# G020H.net
KiCad netlist of a schematic drawn in EAGLE
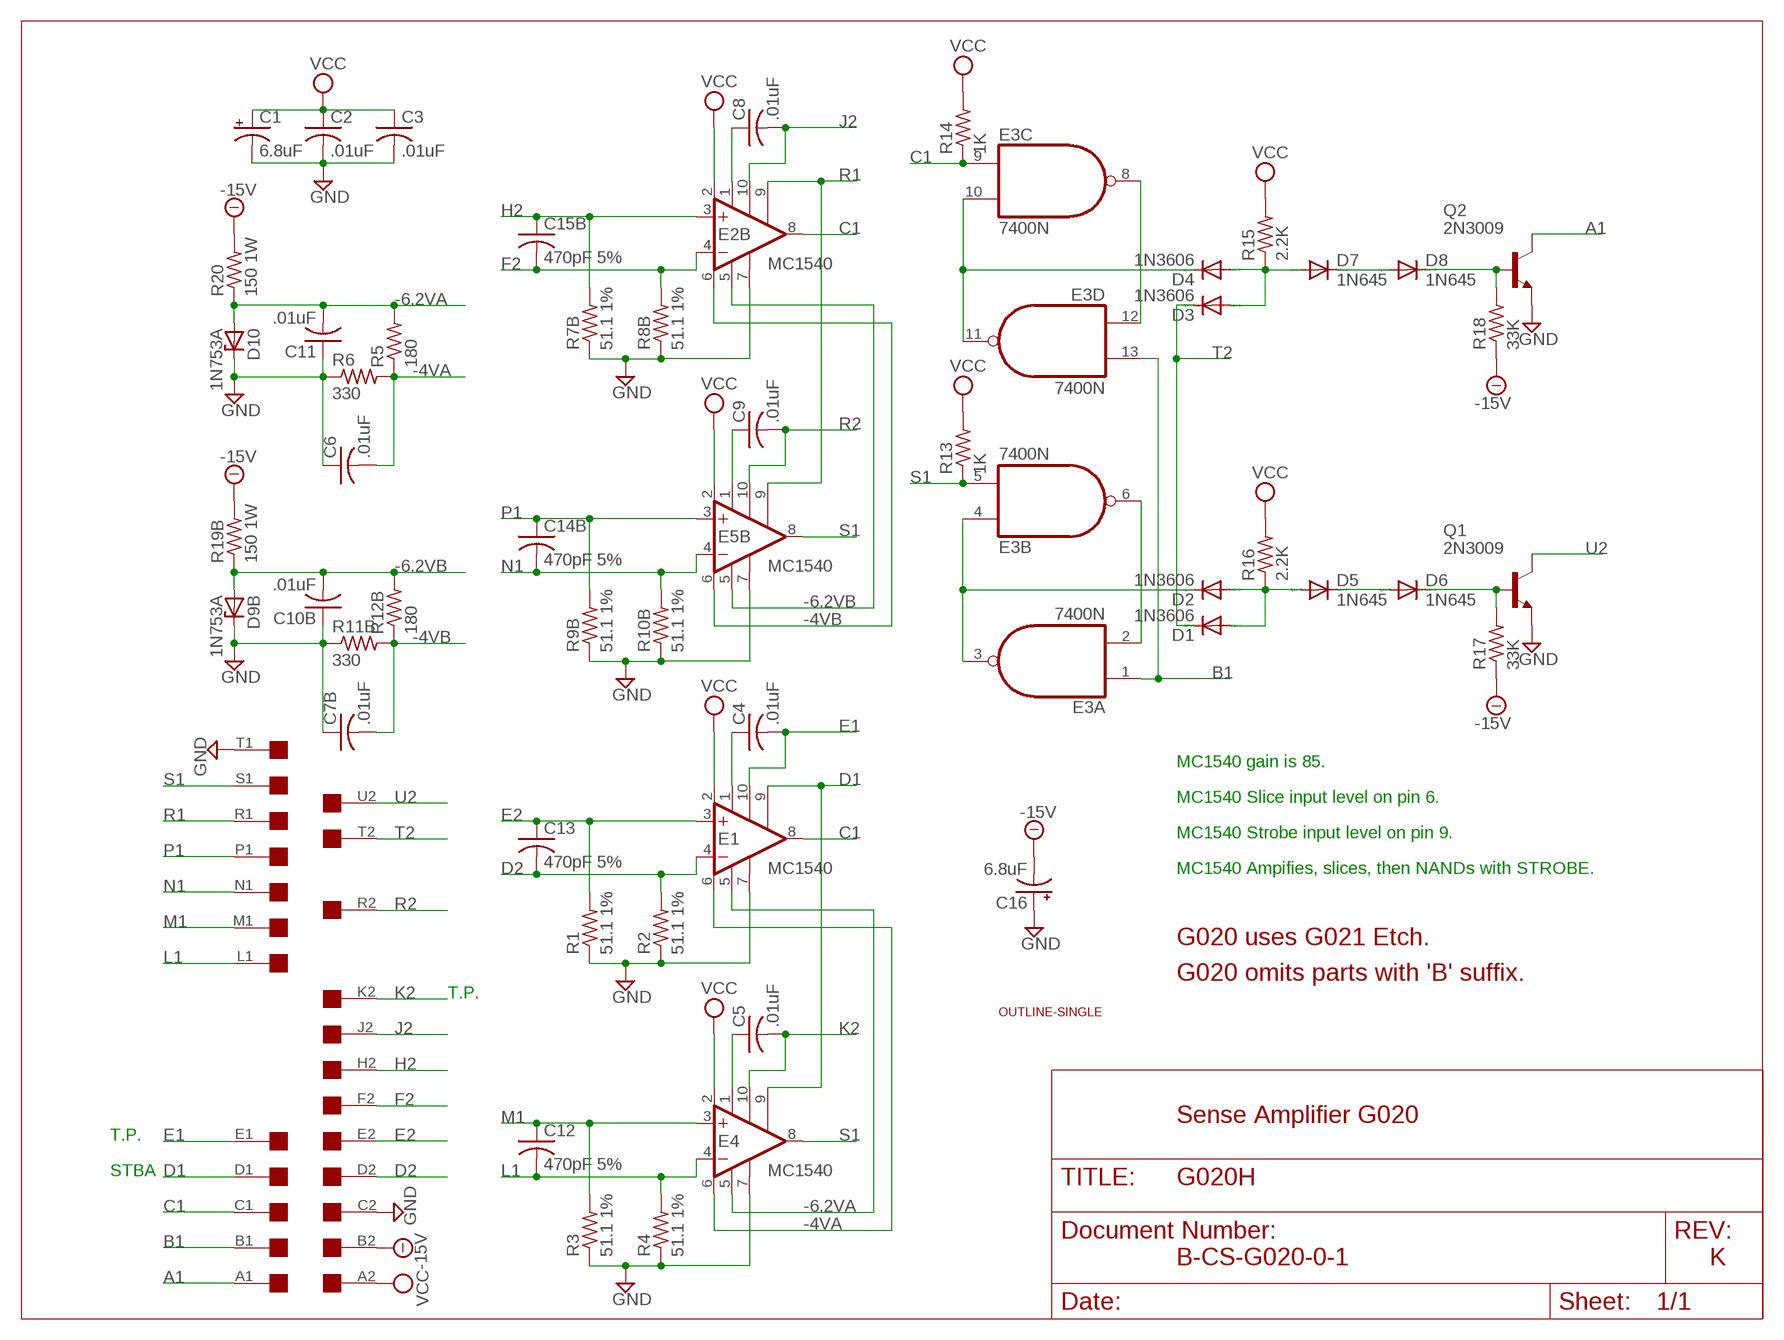
[diagram p0: schematic, sheet 1]

(export (version "E")
  (design (tool "Eeschema 10.0.6"))
  (components
    (comp (ref "C1")
      (value "6.8uF")
      (footprint "eagle-import:E12-8")
      (libsource (lib "eagle-import") (part "CPOL-USE20-8AXIAL"))
    )
    (comp (ref "C2")
      (value ".01uF")
      (footprint "eagle-import:C050-025X075")
      (libsource (lib "eagle-import") (part "C-US050-025X075"))
    )
    (comp (ref "C3")
      (value ".01uF")
      (footprint "eagle-import:C050-025X075")
      (libsource (lib "eagle-import") (part "C-US050-025X075"))
    )
    (comp (ref "C4")
      (value ".01uF")
      (footprint "eagle-import:C050-025X075")
      (libsource (lib "eagle-import") (part "C-US050-025X075"))
    )
    (comp (ref "C5")
      (value ".01uF")
      (footprint "eagle-import:C050-025X075")
      (libsource (lib "eagle-import") (part "C-US050-025X075"))
    )
    (comp (ref "C6")
      (value ".01uF")
      (footprint "eagle-import:C050-025X075")
      (libsource (lib "eagle-import") (part "C-US050-025X075"))
    )
    (comp (ref "C7B")
      (value ".01uF")
      (footprint "eagle-import:C050-025X075")
      (libsource (lib "eagle-import") (part "C-US050-025X075"))
    )
    (comp (ref "C8")
      (value ".01uF")
      (footprint "eagle-import:C050-025X075")
      (libsource (lib "eagle-import") (part "C-US050-025X075"))
    )
    (comp (ref "C9")
      (value ".01uF")
      (footprint "eagle-import:C050-025X075")
      (libsource (lib "eagle-import") (part "C-US050-025X075"))
    )
    (comp (ref "C10B")
      (value ".01uF")
      (footprint "eagle-import:C050-025X075")
      (libsource (lib "eagle-import") (part "C-US050-025X075"))
    )
    (comp (ref "C11")
      (value ".01uF")
      (footprint "eagle-import:C050-025X075")
      (libsource (lib "eagle-import") (part "C-US050-025X075"))
    )
    (comp (ref "C12")
      (value "470pF 5%")
      (footprint "eagle-import:C050-025X075")
      (libsource (lib "eagle-import") (part "C-US050-025X075"))
    )
    (comp (ref "C13")
      (value "470pF 5%")
      (footprint "eagle-import:C050-025X075")
      (libsource (lib "eagle-import") (part "C-US050-025X075"))
    )
    (comp (ref "C14B")
      (value "470pF 5%")
      (footprint "eagle-import:C050-025X075")
      (libsource (lib "eagle-import") (part "C-US050-025X075"))
    )
    (comp (ref "C15B")
      (value "470pF 5%")
      (footprint "eagle-import:C050-025X075")
      (libsource (lib "eagle-import") (part "C-US050-025X075"))
    )
    (comp (ref "C16")
      (value "6.8uF")
      (footprint "eagle-import:E12-8")
      (libsource (lib "eagle-import") (part "CPOL-USE20-8AXIAL"))
    )
    (comp (ref "D1")
      (value "1N3606")
      (footprint "eagle-import:DO35-10")
      (libsource (lib "eagle-import") (part "1N4148DO35-10"))
    )
    (comp (ref "D2")
      (value "1N3606")
      (footprint "eagle-import:DO35-10")
      (libsource (lib "eagle-import") (part "1N4148DO35-10"))
    )
    (comp (ref "D3")
      (value "1N3606")
      (footprint "eagle-import:DO35-10")
      (libsource (lib "eagle-import") (part "1N4148DO35-10"))
    )
    (comp (ref "D4")
      (value "1N3606")
      (footprint "eagle-import:DO35-10")
      (libsource (lib "eagle-import") (part "1N4148DO35-10"))
    )
    (comp (ref "D5")
      (value "1N645")
      (footprint "eagle-import:DO35-10")
      (libsource (lib "eagle-import") (part "1N4148DO35-10"))
    )
    (comp (ref "D6")
      (value "1N645")
      (footprint "eagle-import:DO35-10")
      (libsource (lib "eagle-import") (part "1N4148DO35-10"))
    )
    (comp (ref "D7")
      (value "1N645")
      (footprint "eagle-import:DO35-10")
      (libsource (lib "eagle-import") (part "1N4148DO35-10"))
    )
    (comp (ref "D8")
      (value "1N645")
      (footprint "eagle-import:DO35-10")
      (libsource (lib "eagle-import") (part "1N4148DO35-10"))
    )
    (comp (ref "D9B")
      (value "1N753A")
      (footprint "eagle-import:DO35Z10")
      (libsource (lib "eagle-import") (part "ZENER-DIODEDO35Z10"))
    )
    (comp (ref "D10")
      (value "1N753A")
      (footprint "eagle-import:DO35Z10")
      (libsource (lib "eagle-import") (part "ZENER-DIODEDO35Z10"))
    )
    (comp (ref "E1")
      (value "MC1540")
      (footprint "eagle-import:602B")
      (libsource (lib "eagle-import") (part "MC1540G"))
    )
    (comp (ref "E2B")
      (value "MC1540")
      (footprint "eagle-import:602B")
      (libsource (lib "eagle-import") (part "MC1540G"))
    )
    (comp (ref "E3")
      (value "7400N")
      (footprint "eagle-import:DIL14")
      (libsource (lib "eagle-import") (part "7400N"))
    )
    (comp (ref "E4")
      (value "MC1540")
      (footprint "eagle-import:602B")
      (libsource (lib "eagle-import") (part "MC1540G"))
    )
    (comp (ref "E5B")
      (value "MC1540")
      (footprint "eagle-import:602B")
      (libsource (lib "eagle-import") (part "MC1540G"))
    )
    (comp (ref "Q1")
      (value "2N3009")
      (footprint "eagle-import:TO5")
      (libsource (lib "eagle-import") (part "2N2219"))
    )
    (comp (ref "Q2")
      (value "2N3009")
      (footprint "eagle-import:TO5")
      (libsource (lib "eagle-import") (part "2N2219"))
    )
    (comp (ref "R1")
      (value "51.1 1%")
      (footprint "eagle-import:0207_15")
      (libsource (lib "eagle-import") (part "R-US_0207/15"))
    )
    (comp (ref "R2")
      (value "51.1 1%")
      (footprint "eagle-import:0207_15")
      (libsource (lib "eagle-import") (part "R-US_0207/15"))
    )
    (comp (ref "R3")
      (value "51.1 1%")
      (footprint "eagle-import:0207_15")
      (libsource (lib "eagle-import") (part "R-US_0207/15"))
    )
    (comp (ref "R4")
      (value "51.1 1%")
      (footprint "eagle-import:0207_15")
      (libsource (lib "eagle-import") (part "R-US_0207/15"))
    )
    (comp (ref "R5")
      (value "180")
      (footprint "eagle-import:0207_10")
      (libsource (lib "eagle-import") (part "R-US_0207/10"))
    )
    (comp (ref "R6")
      (value "330")
      (footprint "eagle-import:0207_10")
      (libsource (lib "eagle-import") (part "R-US_0207/10"))
    )
    (comp (ref "R7B")
      (value "51.1 1%")
      (footprint "eagle-import:0207_15")
      (libsource (lib "eagle-import") (part "R-US_0207/15"))
    )
    (comp (ref "R8B")
      (value "51.1 1%")
      (footprint "eagle-import:0207_15")
      (libsource (lib "eagle-import") (part "R-US_0207/15"))
    )
    (comp (ref "R9B")
      (value "51.1 1%")
      (footprint "eagle-import:0207_15")
      (libsource (lib "eagle-import") (part "R-US_0207/15"))
    )
    (comp (ref "R10B")
      (value "51.1 1%")
      (footprint "eagle-import:0207_15")
      (libsource (lib "eagle-import") (part "R-US_0207/15"))
    )
    (comp (ref "R11B")
      (value "330")
      (footprint "eagle-import:0207_10")
      (libsource (lib "eagle-import") (part "R-US_0207/10"))
    )
    (comp (ref "R12B")
      (value "180")
      (footprint "eagle-import:0207_10")
      (libsource (lib "eagle-import") (part "R-US_0207/10"))
    )
    (comp (ref "R13")
      (value "1K")
      (footprint "eagle-import:0207_10")
      (libsource (lib "eagle-import") (part "R-US_0207/10"))
    )
    (comp (ref "R14")
      (value "1K")
      (footprint "eagle-import:0207_10")
      (libsource (lib "eagle-import") (part "R-US_0207/10"))
    )
    (comp (ref "R15")
      (value "2.2K")
      (footprint "eagle-import:0207_10")
      (libsource (lib "eagle-import") (part "R-US_0207/10"))
    )
    (comp (ref "R16")
      (value "2.2K")
      (footprint "eagle-import:0207_10")
      (libsource (lib "eagle-import") (part "R-US_0207/10"))
    )
    (comp (ref "R17")
      (value "33K")
      (footprint "eagle-import:0207_10")
      (libsource (lib "eagle-import") (part "R-US_0207/10"))
    )
    (comp (ref "R18")
      (value "33K")
      (footprint "eagle-import:0207_10")
      (libsource (lib "eagle-import") (part "R-US_0207/10"))
    )
    (comp (ref "R19B")
      (value "150 1W")
      (footprint "eagle-import:0414_20")
      (libsource (lib "eagle-import") (part "R-US_0414/20"))
    )
    (comp (ref "R20")
      (value "150 1W")
      (footprint "eagle-import:0414_20")
      (libsource (lib "eagle-import") (part "R-US_0414/20"))
    )
    (comp (ref "U$1")
      (value "SINGLE")
      (footprint "eagle-import:EDGE-CON2")
      (libsource (lib "eagle-import") (part "SINGLE"))
    )
    (comp (ref "U$2")
      (value "OUTLINE-SINGLE")
      (footprint "eagle-import:SINGLE")
      (libsource (lib "eagle-import") (part "OUTLINE-SINGLE"))
    )
  )
  (nets
    (net (code "1") (name "-15V") (class "Default")
      (node (ref "C16") (pin "-") (pinfunction "-_-") (pintype "passive"))
      (node (ref "R17") (pin "1") (pinfunction "1_1") (pintype "passive"))
      (node (ref "R18") (pin "1") (pinfunction "1_1") (pintype "passive"))
      (node (ref "R19B") (pin "2") (pinfunction "2_2") (pintype "passive"))
      (node (ref "R20") (pin "2") (pinfunction "2_2") (pintype "passive"))
      (node (ref "U$1") (pin "B2") (pinfunction "1_B2") (pintype "bidirectional"))
    )
    (net (code "2") (name "/-4VA") (class "Default")
      (node (ref "C6") (pin "2") (pinfunction "2_2") (pintype "passive"))
      (node (ref "E1") (pin "6") (pinfunction "SLICE_6") (pintype "bidirectional"))
      (node (ref "E4") (pin "6") (pinfunction "SLICE_6") (pintype "bidirectional"))
      (node (ref "R5") (pin "1") (pinfunction "1_1") (pintype "passive"))
      (node (ref "R6") (pin "2") (pinfunction "2_2") (pintype "passive"))
    )
    (net (code "3") (name "/-4VB") (class "Default")
      (node (ref "C7B") (pin "2") (pinfunction "2_2") (pintype "passive"))
      (node (ref "E2B") (pin "6") (pinfunction "SLICE_6") (pintype "bidirectional"))
      (node (ref "E5B") (pin "6") (pinfunction "SLICE_6") (pintype "bidirectional"))
      (node (ref "R11B") (pin "2") (pinfunction "2_2") (pintype "passive"))
      (node (ref "R12B") (pin "1") (pinfunction "1_1") (pintype "passive"))
    )
    (net (code "4") (name "/-6.2VA") (class "Default")
      (node (ref "C11") (pin "2") (pinfunction "2_2") (pintype "passive"))
      (node (ref "D10") (pin "A") (pinfunction "A_A") (pintype "passive"))
      (node (ref "E1") (pin "5") (pinfunction "V-_5") (pintype "power_in"))
      (node (ref "E4") (pin "5") (pinfunction "V-_5") (pintype "power_in"))
      (node (ref "R20") (pin "1") (pinfunction "1_1") (pintype "passive"))
      (node (ref "R5") (pin "2") (pinfunction "2_2") (pintype "passive"))
    )
    (net (code "5") (name "/-6.2VB") (class "Default")
      (node (ref "C10B") (pin "2") (pinfunction "2_2") (pintype "passive"))
      (node (ref "D9B") (pin "A") (pinfunction "A_A") (pintype "passive"))
      (node (ref "E2B") (pin "5") (pinfunction "V-_5") (pintype "power_in"))
      (node (ref "E5B") (pin "5") (pinfunction "V-_5") (pintype "power_in"))
      (node (ref "R12B") (pin "2") (pinfunction "2_2") (pintype "passive"))
      (node (ref "R19B") (pin "1") (pinfunction "1_1") (pintype "passive"))
    )
    (net (code "6") (name "/A1") (class "Default")
      (node (ref "Q2") (pin "3") (pinfunction "C_3") (pintype "passive"))
      (node (ref "U$1") (pin "A1") (pinfunction "1_A1") (pintype "bidirectional"))
    )
    (net (code "7") (name "/B1") (class "Default")
      (node (ref "E3") (pin "1") (pinfunction "I0_1") (pintype "input"))
      (node (ref "E3") (pin "13") (pinfunction "I1_13") (pintype "input"))
      (node (ref "U$1") (pin "B1") (pinfunction "1_B1") (pintype "bidirectional"))
    )
    (net (code "8") (name "/C1") (class "Default")
      (node (ref "E1") (pin "8") (pinfunction "OUT_8") (pintype "open_collector"))
      (node (ref "E2B") (pin "8") (pinfunction "OUT_8") (pintype "open_collector"))
      (node (ref "E3") (pin "9") (pinfunction "I0_9") (pintype "input"))
      (node (ref "R14") (pin "1") (pinfunction "1_1") (pintype "passive"))
      (node (ref "U$1") (pin "C1") (pinfunction "1_C1") (pintype "bidirectional"))
    )
    (net (code "9") (name "/D1") (class "Default")
      (node (ref "E1") (pin "9") (pinfunction "ISTROBE_9") (pintype "passive"))
      (node (ref "E4") (pin "9") (pinfunction "ISTROBE_9") (pintype "passive"))
      (node (ref "U$1") (pin "D1") (pinfunction "1_D1") (pintype "bidirectional"))
    )
    (net (code "10") (name "/D2") (class "Default")
      (node (ref "C13") (pin "2") (pinfunction "2_2") (pintype "passive"))
      (node (ref "E1") (pin "4") (pinfunction "-IN_4") (pintype "input"))
      (node (ref "R2") (pin "2") (pinfunction "2_2") (pintype "passive"))
      (node (ref "U$1") (pin "D2") (pinfunction "1_D2") (pintype "bidirectional"))
    )
    (net (code "11") (name "/E1") (class "Default")
      (node (ref "C4") (pin "2") (pinfunction "2_2") (pintype "passive"))
      (node (ref "E1") (pin "10") (pinfunction "CEXTB_10") (pintype "passive"))
      (node (ref "U$1") (pin "E1") (pinfunction "1_E1") (pintype "bidirectional"))
    )
    (net (code "12") (name "/E2") (class "Default")
      (node (ref "C13") (pin "1") (pinfunction "1_1") (pintype "passive"))
      (node (ref "E1") (pin "3") (pinfunction "+IN_3") (pintype "input"))
      (node (ref "R1") (pin "2") (pinfunction "2_2") (pintype "passive"))
      (node (ref "U$1") (pin "E2") (pinfunction "1_E2") (pintype "bidirectional"))
    )
    (net (code "13") (name "/F2") (class "Default")
      (node (ref "C15B") (pin "2") (pinfunction "2_2") (pintype "passive"))
      (node (ref "E2B") (pin "4") (pinfunction "-IN_4") (pintype "input"))
      (node (ref "R8B") (pin "2") (pinfunction "2_2") (pintype "passive"))
      (node (ref "U$1") (pin "F2") (pinfunction "1_F2") (pintype "bidirectional"))
    )
    (net (code "14") (name "/H2") (class "Default")
      (node (ref "C15B") (pin "1") (pinfunction "1_1") (pintype "passive"))
      (node (ref "E2B") (pin "3") (pinfunction "+IN_3") (pintype "input"))
      (node (ref "R7B") (pin "2") (pinfunction "2_2") (pintype "passive"))
      (node (ref "U$1") (pin "H2") (pinfunction "1_H2") (pintype "bidirectional"))
    )
    (net (code "15") (name "/J2") (class "Default")
      (node (ref "C8") (pin "2") (pinfunction "2_2") (pintype "passive"))
      (node (ref "E2B") (pin "10") (pinfunction "CEXTB_10") (pintype "passive"))
      (node (ref "U$1") (pin "J2") (pinfunction "1_J2") (pintype "bidirectional"))
    )
    (net (code "16") (name "/K2") (class "Default")
      (node (ref "C5") (pin "2") (pinfunction "2_2") (pintype "passive"))
      (node (ref "E4") (pin "10") (pinfunction "CEXTB_10") (pintype "passive"))
      (node (ref "U$1") (pin "K2") (pinfunction "1_K2") (pintype "bidirectional"))
    )
    (net (code "17") (name "/L1") (class "Default")
      (node (ref "C12") (pin "2") (pinfunction "2_2") (pintype "passive"))
      (node (ref "E4") (pin "4") (pinfunction "-IN_4") (pintype "input"))
      (node (ref "R4") (pin "2") (pinfunction "2_2") (pintype "passive"))
      (node (ref "U$1") (pin "L1") (pinfunction "1_L1") (pintype "bidirectional"))
    )
    (net (code "18") (name "/M1") (class "Default")
      (node (ref "C12") (pin "1") (pinfunction "1_1") (pintype "passive"))
      (node (ref "E4") (pin "3") (pinfunction "+IN_3") (pintype "input"))
      (node (ref "R3") (pin "2") (pinfunction "2_2") (pintype "passive"))
      (node (ref "U$1") (pin "M1") (pinfunction "1_M1") (pintype "bidirectional"))
    )
    (net (code "19") (name "/N1") (class "Default")
      (node (ref "C14B") (pin "2") (pinfunction "2_2") (pintype "passive"))
      (node (ref "E5B") (pin "4") (pinfunction "-IN_4") (pintype "input"))
      (node (ref "R10B") (pin "2") (pinfunction "2_2") (pintype "passive"))
      (node (ref "U$1") (pin "N1") (pinfunction "1_N1") (pintype "bidirectional"))
    )
    (net (code "20") (name "/P1") (class "Default")
      (node (ref "C14B") (pin "1") (pinfunction "1_1") (pintype "passive"))
      (node (ref "E5B") (pin "3") (pinfunction "+IN_3") (pintype "input"))
      (node (ref "R9B") (pin "2") (pinfunction "2_2") (pintype "passive"))
      (node (ref "U$1") (pin "P1") (pinfunction "1_P1") (pintype "bidirectional"))
    )
    (net (code "21") (name "/R1") (class "Default")
      (node (ref "E2B") (pin "9") (pinfunction "ISTROBE_9") (pintype "passive"))
      (node (ref "E5B") (pin "9") (pinfunction "ISTROBE_9") (pintype "passive"))
      (node (ref "U$1") (pin "R1") (pinfunction "1_R1") (pintype "bidirectional"))
    )
    (net (code "22") (name "/R2") (class "Default")
      (node (ref "C9") (pin "2") (pinfunction "2_2") (pintype "passive"))
      (node (ref "E5B") (pin "10") (pinfunction "CEXTB_10") (pintype "passive"))
      (node (ref "U$1") (pin "R2") (pinfunction "1_R2") (pintype "bidirectional"))
    )
    (net (code "23") (name "/S1") (class "Default")
      (node (ref "E3") (pin "5") (pinfunction "I1_5") (pintype "input"))
      (node (ref "E4") (pin "8") (pinfunction "OUT_8") (pintype "open_collector"))
      (node (ref "E5B") (pin "8") (pinfunction "OUT_8") (pintype "open_collector"))
      (node (ref "R13") (pin "1") (pinfunction "1_1") (pintype "passive"))
      (node (ref "U$1") (pin "S1") (pinfunction "1_S1") (pintype "bidirectional"))
    )
    (net (code "24") (name "/T2") (class "Default")
      (node (ref "D1") (pin "C") (pinfunction "C_C") (pintype "passive"))
      (node (ref "D3") (pin "C") (pinfunction "C_C") (pintype "passive"))
      (node (ref "U$1") (pin "T2") (pinfunction "1_T2") (pintype "bidirectional"))
    )
    (net (code "25") (name "/U2") (class "Default")
      (node (ref "Q1") (pin "3") (pinfunction "C_3") (pintype "passive"))
      (node (ref "U$1") (pin "U2") (pinfunction "1_U2") (pintype "bidirectional"))
    )
    (net (code "26") (name "GND") (class "Default")
      (node (ref "C1") (pin "-") (pinfunction "-_-") (pintype "passive"))
      (node (ref "C10B") (pin "1") (pinfunction "1_1") (pintype "passive"))
      (node (ref "C11") (pin "1") (pinfunction "1_1") (pintype "passive"))
      (node (ref "C16") (pin "+") (pinfunction "+_+") (pintype "passive"))
      (node (ref "C2") (pin "2") (pinfunction "2_2") (pintype "passive"))
      (node (ref "C3") (pin "2") (pinfunction "2_2") (pintype "passive"))
      (node (ref "C6") (pin "1") (pinfunction "1_1") (pintype "passive"))
      (node (ref "C7B") (pin "1") (pinfunction "1_1") (pintype "passive"))
      (node (ref "D10") (pin "C") (pinfunction "C_C") (pintype "passive"))
      (node (ref "D9B") (pin "C") (pinfunction "C_C") (pintype "passive"))
      (node (ref "E1") (pin "7") (pinfunction "GND_7") (pintype "power_in"))
      (node (ref "E2B") (pin "7") (pinfunction "GND_7") (pintype "power_in"))
      (node (ref "E4") (pin "7") (pinfunction "GND_7") (pintype "power_in"))
      (node (ref "E5B") (pin "7") (pinfunction "GND_7") (pintype "power_in"))
      (node (ref "Q1") (pin "1") (pinfunction "E_1") (pintype "passive"))
      (node (ref "Q2") (pin "1") (pinfunction "E_1") (pintype "passive"))
      (node (ref "R1") (pin "1") (pinfunction "1_1") (pintype "passive"))
      (node (ref "R10B") (pin "1") (pinfunction "1_1") (pintype "passive"))
      (node (ref "R11B") (pin "1") (pinfunction "1_1") (pintype "passive"))
      (node (ref "R2") (pin "1") (pinfunction "1_1") (pintype "passive"))
      (node (ref "R3") (pin "1") (pinfunction "1_1") (pintype "passive"))
      (node (ref "R4") (pin "1") (pinfunction "1_1") (pintype "passive"))
      (node (ref "R6") (pin "1") (pinfunction "1_1") (pintype "passive"))
      (node (ref "R7B") (pin "1") (pinfunction "1_1") (pintype "passive"))
      (node (ref "R8B") (pin "1") (pinfunction "1_1") (pintype "passive"))
      (node (ref "R9B") (pin "1") (pinfunction "1_1") (pintype "passive"))
      (node (ref "U$1") (pin "C2") (pinfunction "1_C2") (pintype "bidirectional"))
      (node (ref "U$1") (pin "T1") (pinfunction "1_T1") (pintype "bidirectional"))
    )
    (net (code "27") (name "Net-(D1-PadA)") (class "Default")
      (node (ref "D1") (pin "A") (pinfunction "A_A") (pintype "passive"))
      (node (ref "D2") (pin "A") (pinfunction "A_A") (pintype "passive"))
      (node (ref "D5") (pin "A") (pinfunction "A_A") (pintype "passive"))
      (node (ref "R16") (pin "1") (pinfunction "1_1") (pintype "passive"))
    )
    (net (code "28") (name "Net-(D3-PadA)") (class "Default")
      (node (ref "D3") (pin "A") (pinfunction "A_A") (pintype "passive"))
      (node (ref "D4") (pin "A") (pinfunction "A_A") (pintype "passive"))
      (node (ref "D7") (pin "A") (pinfunction "A_A") (pintype "passive"))
      (node (ref "R15") (pin "1") (pinfunction "1_1") (pintype "passive"))
    )
    (net (code "29") (name "Net-(D5-PadC)") (class "Default")
      (node (ref "D5") (pin "C") (pinfunction "C_C") (pintype "passive"))
      (node (ref "D6") (pin "A") (pinfunction "A_A") (pintype "passive"))
    )
    (net (code "30") (name "Net-(D7-PadC)") (class "Default")
      (node (ref "D7") (pin "C") (pinfunction "C_C") (pintype "passive"))
      (node (ref "D8") (pin "A") (pinfunction "A_A") (pintype "passive"))
    )
    (net (code "31") (name "Net-(E1-CEXTA)") (class "Default")
      (node (ref "C4") (pin "1") (pinfunction "1_1") (pintype "passive"))
      (node (ref "E1") (pin "1") (pinfunction "CEXTA_1") (pintype "passive"))
    )
    (net (code "32") (name "Net-(E2B-CEXTA)") (class "Default")
      (node (ref "C8") (pin "1") (pinfunction "1_1") (pintype "passive"))
      (node (ref "E2B") (pin "1") (pinfunction "CEXTA_1") (pintype "passive"))
    )
    (net (code "33") (name "Net-(E3A-I1)") (class "Default")
      (node (ref "E3") (pin "2") (pinfunction "I1_2") (pintype "input"))
      (node (ref "E3") (pin "6") (pinfunction "O_6") (pintype "output"))
    )
    (net (code "34") (name "Net-(E3A-O)") (class "Default")
      (node (ref "D2") (pin "C") (pinfunction "C_C") (pintype "passive"))
      (node (ref "E3") (pin "3") (pinfunction "O_3") (pintype "output"))
      (node (ref "E3") (pin "4") (pinfunction "I0_4") (pintype "input"))
    )
    (net (code "35") (name "Net-(E3C-I1)") (class "Default")
      (node (ref "D4") (pin "C") (pinfunction "C_C") (pintype "passive"))
      (node (ref "E3") (pin "10") (pinfunction "I1_10") (pintype "input"))
      (node (ref "E3") (pin "11") (pinfunction "O_11") (pintype "output"))
    )
    (net (code "36") (name "Net-(E3C-O)") (class "Default")
      (node (ref "E3") (pin "12") (pinfunction "I0_12") (pintype "input"))
      (node (ref "E3") (pin "8") (pinfunction "O_8") (pintype "output"))
    )
    (net (code "37") (name "Net-(E4-CEXTA)") (class "Default")
      (node (ref "C5") (pin "1") (pinfunction "1_1") (pintype "passive"))
      (node (ref "E4") (pin "1") (pinfunction "CEXTA_1") (pintype "passive"))
    )
    (net (code "38") (name "Net-(E5B-CEXTA)") (class "Default")
      (node (ref "C9") (pin "1") (pinfunction "1_1") (pintype "passive"))
      (node (ref "E5B") (pin "1") (pinfunction "CEXTA_1") (pintype "passive"))
    )
    (net (code "39") (name "Net-(Q1-B)") (class "Default")
      (node (ref "D6") (pin "C") (pinfunction "C_C") (pintype "passive"))
      (node (ref "Q1") (pin "2") (pinfunction "B_2") (pintype "passive"))
      (node (ref "R17") (pin "2") (pinfunction "2_2") (pintype "passive"))
    )
    (net (code "40") (name "Net-(Q2-B)") (class "Default")
      (node (ref "D8") (pin "C") (pinfunction "C_C") (pintype "passive"))
      (node (ref "Q2") (pin "2") (pinfunction "B_2") (pintype "passive"))
      (node (ref "R18") (pin "2") (pinfunction "2_2") (pintype "passive"))
    )
    (net (code "41") (name "VCC") (class "Default")
      (node (ref "C1") (pin "+") (pinfunction "+_+") (pintype "passive"))
      (node (ref "C2") (pin "1") (pinfunction "1_1") (pintype "passive"))
      (node (ref "C3") (pin "1") (pinfunction "1_1") (pintype "passive"))
      (node (ref "E1") (pin "2") (pinfunction "V+_2") (pintype "power_in"))
      (node (ref "E2B") (pin "2") (pinfunction "V+_2") (pintype "power_in"))
      (node (ref "E4") (pin "2") (pinfunction "V+_2") (pintype "power_in"))
      (node (ref "E5B") (pin "2") (pinfunction "V+_2") (pintype "power_in"))
      (node (ref "R13") (pin "2") (pinfunction "2_2") (pintype "passive"))
      (node (ref "R14") (pin "2") (pinfunction "2_2") (pintype "passive"))
      (node (ref "R15") (pin "2") (pinfunction "2_2") (pintype "passive"))
      (node (ref "R16") (pin "2") (pinfunction "2_2") (pintype "passive"))
      (node (ref "U$1") (pin "A2") (pinfunction "1_A2") (pintype "bidirectional"))
    )
  )
)
